# VSOP_DQM_DQE.net
KiCad netlist of a schematic drawn in EAGLE
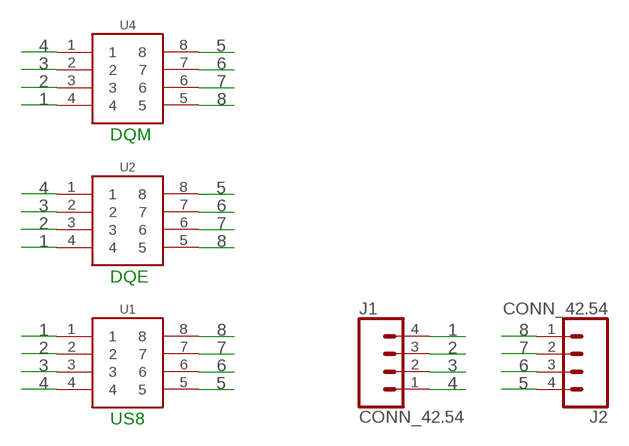
[diagram p0: schematic, sheet 1]

(export (version "E")
  (design (tool "Eeschema 10.0.6"))
  (components
    (comp (ref "J1")
      (value "CONN_42.54")
      (footprint "eagle-import:1X04")
      (libsource (lib "eagle-import") (part "CONN_42.54"))
    )
    (comp (ref "J2")
      (value "CONN_42.54")
      (footprint "eagle-import:1X04")
      (libsource (lib "eagle-import") (part "CONN_42.54"))
    )
    (comp (ref "U1")
      (value "GEN_8VSOP")
      (footprint "eagle-import:DCU_(R-PDSO-G8)")
      (libsource (lib "eagle-import") (part "GEN_8VSOP"))
    )
    (comp (ref "U2")
      (value "GEN_8DQE")
      (footprint "eagle-import:DQE_R-PX2SON-N8")
      (libsource (lib "eagle-import") (part "GEN_8DQE"))
    )
    (comp (ref "U4")
      (value "GEN_8DQM")
      (footprint "eagle-import:DQM_R-PX2SON-N8")
      (libsource (lib "eagle-import") (part "GEN_8DQM"))
    )
  )
  (nets
    (net (code "1") (name "/1") (class "Default")
      (node (ref "J1") (pin "4") (pinfunction "4_4") (pintype "passive"))
      (node (ref "U1") (pin "1") (pinfunction "1_1") (pintype "bidirectional"))
      (node (ref "U2") (pin "4") (pinfunction "4_4") (pintype "bidirectional"))
      (node (ref "U4") (pin "4") (pinfunction "4_4") (pintype "bidirectional"))
    )
    (net (code "2") (name "/2") (class "Default")
      (node (ref "J1") (pin "3") (pinfunction "3_3") (pintype "passive"))
      (node (ref "U1") (pin "2") (pinfunction "2_2") (pintype "bidirectional"))
      (node (ref "U2") (pin "3") (pinfunction "3_3") (pintype "bidirectional"))
      (node (ref "U4") (pin "3") (pinfunction "3_3") (pintype "bidirectional"))
    )
    (net (code "3") (name "/3") (class "Default")
      (node (ref "J1") (pin "2") (pinfunction "2_2") (pintype "passive"))
      (node (ref "U1") (pin "3") (pinfunction "3_3") (pintype "bidirectional"))
      (node (ref "U2") (pin "2") (pinfunction "2_2") (pintype "bidirectional"))
      (node (ref "U4") (pin "2") (pinfunction "2_2") (pintype "bidirectional"))
    )
    (net (code "4") (name "/4") (class "Default")
      (node (ref "J1") (pin "1") (pinfunction "1_1") (pintype "passive"))
      (node (ref "U1") (pin "4") (pinfunction "4_4") (pintype "bidirectional"))
      (node (ref "U2") (pin "1") (pinfunction "1_1") (pintype "bidirectional"))
      (node (ref "U4") (pin "1") (pinfunction "1_1") (pintype "bidirectional"))
    )
    (net (code "5") (name "/5") (class "Default")
      (node (ref "J2") (pin "4") (pinfunction "4_4") (pintype "passive"))
      (node (ref "U1") (pin "5") (pinfunction "5_5") (pintype "bidirectional"))
      (node (ref "U2") (pin "8") (pinfunction "8_8") (pintype "bidirectional"))
      (node (ref "U4") (pin "8") (pinfunction "8_8") (pintype "bidirectional"))
    )
    (net (code "6") (name "/6") (class "Default")
      (node (ref "J2") (pin "3") (pinfunction "3_3") (pintype "passive"))
      (node (ref "U1") (pin "6") (pinfunction "6_6") (pintype "bidirectional"))
      (node (ref "U2") (pin "7") (pinfunction "7_7") (pintype "bidirectional"))
      (node (ref "U4") (pin "7") (pinfunction "7_7") (pintype "bidirectional"))
    )
    (net (code "7") (name "/7") (class "Default")
      (node (ref "J2") (pin "2") (pinfunction "2_2") (pintype "passive"))
      (node (ref "U1") (pin "7") (pinfunction "7_7") (pintype "bidirectional"))
      (node (ref "U2") (pin "6") (pinfunction "6_6") (pintype "bidirectional"))
      (node (ref "U4") (pin "6") (pinfunction "6_6") (pintype "bidirectional"))
    )
    (net (code "8") (name "/8") (class "Default")
      (node (ref "J2") (pin "1") (pinfunction "1_1") (pintype "passive"))
      (node (ref "U1") (pin "8") (pinfunction "8_8") (pintype "bidirectional"))
      (node (ref "U2") (pin "5") (pinfunction "5_5") (pintype "bidirectional"))
      (node (ref "U4") (pin "5") (pinfunction "5_5") (pintype "bidirectional"))
    )
  )
)
